# Mechanical.net
KiCad netlist of a schematic drawn in Altium Designer
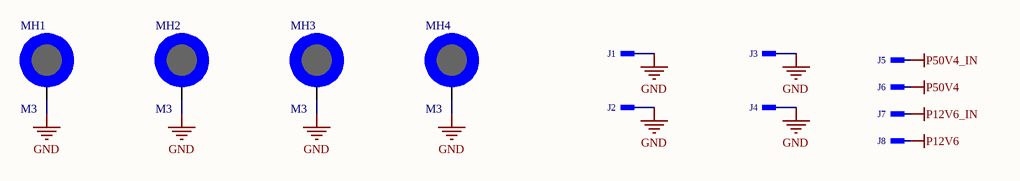
[diagram p0: Mechanical.SchDoc]

(export (version "E")
  (design (tool "Eeschema 10.0.6"))
  (components
    (comp (ref "J1")
      (value "Pad")
      (footprint "PAD_SMD_S1200X500")
      (description "12mm x  5mm SMD Pad with stitches")
      (fields (field (name "AUTHOR") "PC"))
      (libsource (lib "Mechanical And PCB Features") (part "SMD Pad"))
    )
    (comp (ref "J2")
      (value "Pad")
      (footprint "PAD_SMD_S1200X500")
      (description "12mm x  5mm SMD Pad with stitches")
      (fields (field (name "AUTHOR") "PC"))
      (libsource (lib "Mechanical And PCB Features") (part "SMD Pad"))
    )
    (comp (ref "J3")
      (value "Pad")
      (footprint "PAD_SMD_S1200X500")
      (description "12mm x  5mm SMD Pad with stitches")
      (fields (field (name "AUTHOR") "PC"))
      (libsource (lib "Mechanical And PCB Features") (part "SMD Pad"))
    )
    (comp (ref "J4")
      (value "Pad")
      (footprint "PAD_SMD_S1200X500")
      (description "12mm x  5mm SMD Pad with stitches")
      (fields (field (name "AUTHOR") "PC"))
      (libsource (lib "Mechanical And PCB Features") (part "SMD Pad"))
    )
    (comp (ref "J5")
      (value "Pad")
      (footprint "PAD_SMD_S1200X500")
      (description "12mm x  5mm SMD Pad with stitches")
      (fields (field (name "AUTHOR") "PC"))
      (libsource (lib "Mechanical And PCB Features") (part "SMD Pad"))
    )
    (comp (ref "J6")
      (value "Pad")
      (footprint "PAD_SMD_S1200X500")
      (description "12mm x  5mm SMD Pad with stitches")
      (fields (field (name "AUTHOR") "PC"))
      (libsource (lib "Mechanical And PCB Features") (part "SMD Pad"))
    )
    (comp (ref "J7")
      (value "Pad")
      (footprint "PAD_SMD_S1200X500")
      (description "12mm x  5mm SMD Pad with stitches")
      (fields (field (name "AUTHOR") "PC"))
      (libsource (lib "Mechanical And PCB Features") (part "SMD Pad"))
    )
    (comp (ref "J8")
      (value "Pad")
      (footprint "PAD_SMD_S1200X500")
      (description "12mm x  5mm SMD Pad with stitches")
      (fields (field (name "AUTHOR") "PC"))
      (libsource (lib "Mechanical And PCB Features") (part "SMD Pad"))
    )
    (comp (ref "MH1")
      (value "M3")
      (footprint "MH-M3_COPPER_WASHER")
      (description "Mounting hole, M3, exposed pad, space for washer")
      (fields (field (name "AUTHOR") "KB"))
      (libsource (lib "Mechanical And PCB Features") (part "MH"))
    )
    (comp (ref "MH2")
      (value "M3")
      (footprint "MH-M3_COPPER_WASHER")
      (description "Mounting hole, M3, exposed pad, space for washer")
      (fields (field (name "AUTHOR") "KB"))
      (libsource (lib "Mechanical And PCB Features") (part "MH"))
    )
    (comp (ref "MH3")
      (value "M3")
      (footprint "MH-M3_COPPER_WASHER")
      (description "Mounting hole, M3, exposed pad, space for washer")
      (fields (field (name "AUTHOR") "KB"))
      (libsource (lib "Mechanical And PCB Features") (part "MH"))
    )
    (comp (ref "MH4")
      (value "M3")
      (footprint "MH-M3_COPPER_WASHER")
      (description "Mounting hole, M3, exposed pad, space for washer")
      (fields (field (name "AUTHOR") "KB"))
      (libsource (lib "Mechanical And PCB Features") (part "MH"))
    )
  )
  (nets
    (net (code "1") (name "GND") (class "Default")
      (node (ref "J1") (pin "1") (pinfunction "1_1") (pintype "bidirectional"))
      (node (ref "J2") (pin "1") (pinfunction "1_1") (pintype "bidirectional"))
      (node (ref "J3") (pin "1") (pinfunction "1_1") (pintype "bidirectional"))
      (node (ref "J4") (pin "1") (pinfunction "1_1") (pintype "bidirectional"))
      (node (ref "MH1") (pin "MH") (pinfunction "MH_MH") (pintype "passive"))
      (node (ref "MH2") (pin "MH") (pinfunction "MH_MH") (pintype "passive"))
      (node (ref "MH3") (pin "MH") (pinfunction "MH_MH") (pintype "passive"))
      (node (ref "MH4") (pin "MH") (pinfunction "MH_MH") (pintype "passive"))
    )
    (net (code "2") (name "P12V6") (class "Default")
      (node (ref "J8") (pin "1") (pinfunction "1_1") (pintype "bidirectional"))
    )
    (net (code "3") (name "P12V6_IN") (class "Default")
      (node (ref "J7") (pin "1") (pinfunction "1_1") (pintype "bidirectional"))
    )
    (net (code "4") (name "P50V4") (class "Default")
      (node (ref "J6") (pin "1") (pinfunction "1_1") (pintype "bidirectional"))
    )
    (net (code "5") (name "P50V4_IN") (class "Default")
      (node (ref "J5") (pin "1") (pinfunction "1_1") (pintype "bidirectional"))
    )
  )
)
